# usb2ttl.net
KiCad netlist of a schematic drawn in Altium Designer
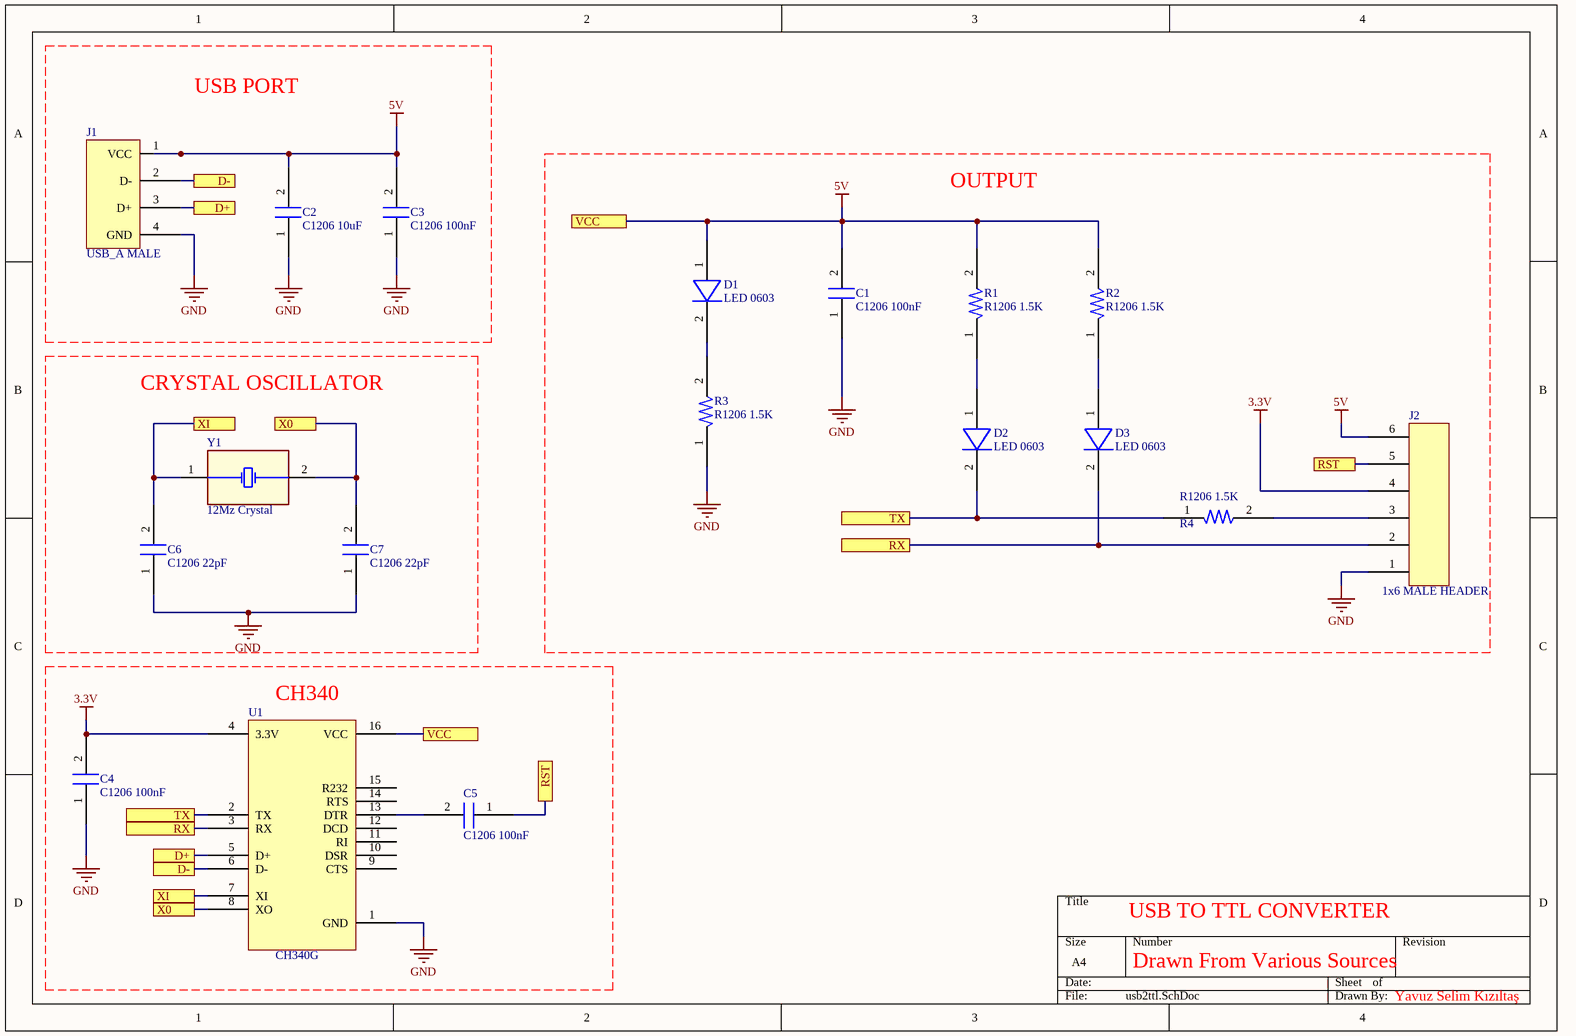
[diagram p0: usb2ttl.SchDoc]

(export (version "E")
  (design (tool "Eeschema 10.0.6"))
  (components
    (comp (ref "C1")
      (value "C1206 100nF")
      (footprint "C1206")
      (libsource (lib "usb2ttl") (part "C1206 100nF"))
    )
    (comp (ref "C2") (value "C1206 10uF") (footprint "C1206") (libsource (lib "usb2ttl") (part "C1206 10uF")))
    (comp (ref "C3")
      (value "C1206 100nF")
      (footprint "C1206")
      (libsource (lib "usb2ttl") (part "C1206 100nF"))
    )
    (comp (ref "C4")
      (value "C1206 100nF")
      (footprint "C1206")
      (libsource (lib "usb2ttl") (part "C1206 100nF"))
    )
    (comp (ref "C5")
      (value "C1206 100nF")
      (footprint "C1206")
      (libsource (lib "usb2ttl") (part "C1206 100nF"))
    )
    (comp (ref "C6") (value "C1206 22pF") (footprint "C1206") (libsource (lib "usb2ttl") (part "C1206 22pF")))
    (comp (ref "C7") (value "C1206 22pF") (footprint "C1206") (libsource (lib "usb2ttl") (part "C1206 22pF")))
    (comp (ref "D1") (value "LED 0603") (footprint "LED 0603") (libsource (lib "usb2ttl") (part "LED 0603")))
    (comp (ref "D2") (value "LED 0603") (footprint "LED 0603") (libsource (lib "usb2ttl") (part "LED 0603")))
    (comp (ref "D3") (value "LED 0603") (footprint "LED 0603") (libsource (lib "usb2ttl") (part "LED 0603")))
    (comp (ref "J1")
      (value "USB_A MALE")
      (footprint "USBA_MALE")
      (libsource (lib "usb2ttl") (part "USB_A MALE"))
    )
    (comp (ref "J2")
      (value "1x6 MALE HEADER")
      (footprint "1x6 MALE HEADER")
      (libsource (lib "usb2ttl") (part "1x6 MALE HEADER"))
    )
    (comp (ref "R1") (value "R1206 1.5K") (footprint "R1206") (libsource (lib "usb2ttl") (part "R1206 1.5K")))
    (comp (ref "R2") (value "R1206 1.5K") (footprint "R1206") (libsource (lib "usb2ttl") (part "R1206 1.5K")))
    (comp (ref "R3") (value "R1206 1.5K") (footprint "R1206") (libsource (lib "usb2ttl") (part "R1206 1.5K")))
    (comp (ref "R4") (value "R1206 1.5K") (footprint "R1206") (libsource (lib "usb2ttl") (part "R1206 1.5K")))
    (comp (ref "U1") (value "CH340G") (footprint "CH340G") (libsource (lib "usb2ttl") (part "CH340G")))
    (comp (ref "Y1")
      (value "12Mz Crystal")
      (footprint "12MHz Crystal")
      (libsource (lib "usb2ttl") (part "12Mz Crystal"))
    )
  )
  (nets
    (net (code "1") (name "/D+") (class "Default")
      (node (ref "J1") (pin "3") (pinfunction "D+_3") (pintype "passive"))
      (node (ref "U1") (pin "5") (pinfunction "D+_5") (pintype "passive"))
    )
    (net (code "2") (name "/D-") (class "Default")
      (node (ref "J1") (pin "2") (pinfunction "D-_2") (pintype "passive"))
      (node (ref "U1") (pin "6") (pinfunction "D-_6") (pintype "passive"))
    )
    (net (code "3") (name "/RST") (class "Default")
      (node (ref "C5") (pin "1") (pintype "passive"))
      (node (ref "J2") (pin "5") (pintype "passive"))
    )
    (net (code "4") (name "/RX") (class "Default")
      (node (ref "D3") (pin "2") (pintype "passive"))
      (node (ref "J2") (pin "2") (pintype "passive"))
      (node (ref "U1") (pin "3") (pinfunction "RX_3") (pintype "passive"))
    )
    (net (code "5") (name "/TX") (class "Default")
      (node (ref "D2") (pin "2") (pintype "passive"))
      (node (ref "R4") (pin "1") (pintype "passive"))
      (node (ref "U1") (pin "2") (pinfunction "TX_2") (pintype "passive"))
    )
    (net (code "6") (name "/X0") (class "Default")
      (node (ref "C7") (pin "2") (pintype "passive"))
      (node (ref "U1") (pin "8") (pinfunction "XO_8") (pintype "passive"))
      (node (ref "Y1") (pin "2") (pintype "power_in"))
    )
    (net (code "7") (name "/XI") (class "Default")
      (node (ref "C6") (pin "2") (pintype "passive"))
      (node (ref "U1") (pin "7") (pinfunction "XI_7") (pintype "passive"))
      (node (ref "Y1") (pin "1") (pintype "power_in"))
    )
    (net (code "8") (name "3.3V") (class "Default")
      (node (ref "C4") (pin "2") (pintype "passive"))
      (node (ref "J2") (pin "4") (pintype "passive"))
      (node (ref "U1") (pin "4") (pinfunction "3.3V_4") (pintype "passive"))
    )
    (net (code "9") (name "5V") (class "Default")
      (node (ref "C1") (pin "2") (pintype "passive"))
      (node (ref "C2") (pin "2") (pintype "passive"))
      (node (ref "C3") (pin "2") (pintype "passive"))
      (node (ref "D1") (pin "1") (pintype "passive"))
      (node (ref "J1") (pin "1") (pinfunction "VCC_1") (pintype "passive"))
      (node (ref "J2") (pin "6") (pintype "passive"))
      (node (ref "R1") (pin "2") (pintype "passive"))
      (node (ref "R2") (pin "2") (pintype "passive"))
      (node (ref "U1") (pin "16") (pinfunction "VCC_16") (pintype "passive"))
    )
    (net (code "10") (name "GND") (class "Default")
      (node (ref "C1") (pin "1") (pintype "passive"))
      (node (ref "C2") (pin "1") (pintype "passive"))
      (node (ref "C3") (pin "1") (pintype "passive"))
      (node (ref "C4") (pin "1") (pintype "passive"))
      (node (ref "C6") (pin "1") (pintype "passive"))
      (node (ref "C7") (pin "1") (pintype "passive"))
      (node (ref "J1") (pin "4") (pinfunction "GND_4") (pintype "passive"))
      (node (ref "J2") (pin "1") (pintype "passive"))
      (node (ref "R3") (pin "1") (pintype "passive"))
      (node (ref "U1") (pin "1") (pinfunction "GND_1") (pintype "passive"))
    )
    (net (code "11") (name "Net-(D1-Pad2)") (class "Default")
      (node (ref "D1") (pin "2") (pintype "passive"))
      (node (ref "R3") (pin "2") (pintype "passive"))
    )
    (net (code "12") (name "Net-(D2-Pad1)") (class "Default")
      (node (ref "D2") (pin "1") (pintype "passive"))
      (node (ref "R1") (pin "1") (pintype "passive"))
    )
    (net (code "13") (name "Net-(D3-Pad1)") (class "Default")
      (node (ref "D3") (pin "1") (pintype "passive"))
      (node (ref "R2") (pin "1") (pintype "passive"))
    )
    (net (code "14") (name "Net-(J2-Pad3)") (class "Default")
      (node (ref "J2") (pin "3") (pintype "passive"))
      (node (ref "R4") (pin "2") (pintype "passive"))
    )
    (net (code "15") (name "Net-(U1-DTR)") (class "Default")
      (node (ref "C5") (pin "2") (pintype "passive"))
      (node (ref "U1") (pin "13") (pinfunction "DTR_13") (pintype "passive"))
    )
    (net (code "16") (name "unconnected-(U1-CTS-Pad9)") (class "Default")
      (node (ref "U1") (pin "9") (pinfunction "CTS_9") (pintype "passive"))
    )
    (net (code "17") (name "unconnected-(U1-DCD-Pad12)") (class "Default")
      (node (ref "U1") (pin "12") (pinfunction "DCD_12") (pintype "passive"))
    )
    (net (code "18") (name "unconnected-(U1-DSR-Pad10)") (class "Default")
      (node (ref "U1") (pin "10") (pinfunction "DSR_10") (pintype "passive"))
    )
    (net (code "19") (name "unconnected-(U1-R232-Pad15)") (class "Default")
      (node (ref "U1") (pin "15") (pinfunction "R232_15") (pintype "passive"))
    )
    (net (code "20") (name "unconnected-(U1-RI-Pad11)") (class "Default")
      (node (ref "U1") (pin "11") (pinfunction "RI_11") (pintype "passive"))
    )
    (net (code "21") (name "unconnected-(U1-RTS-Pad14)") (class "Default")
      (node (ref "U1") (pin "14") (pinfunction "RTS_14") (pintype "passive"))
    )
  )
)
